# badgezadas.net
KiCad netlist of a schematic drawn in EAGLE
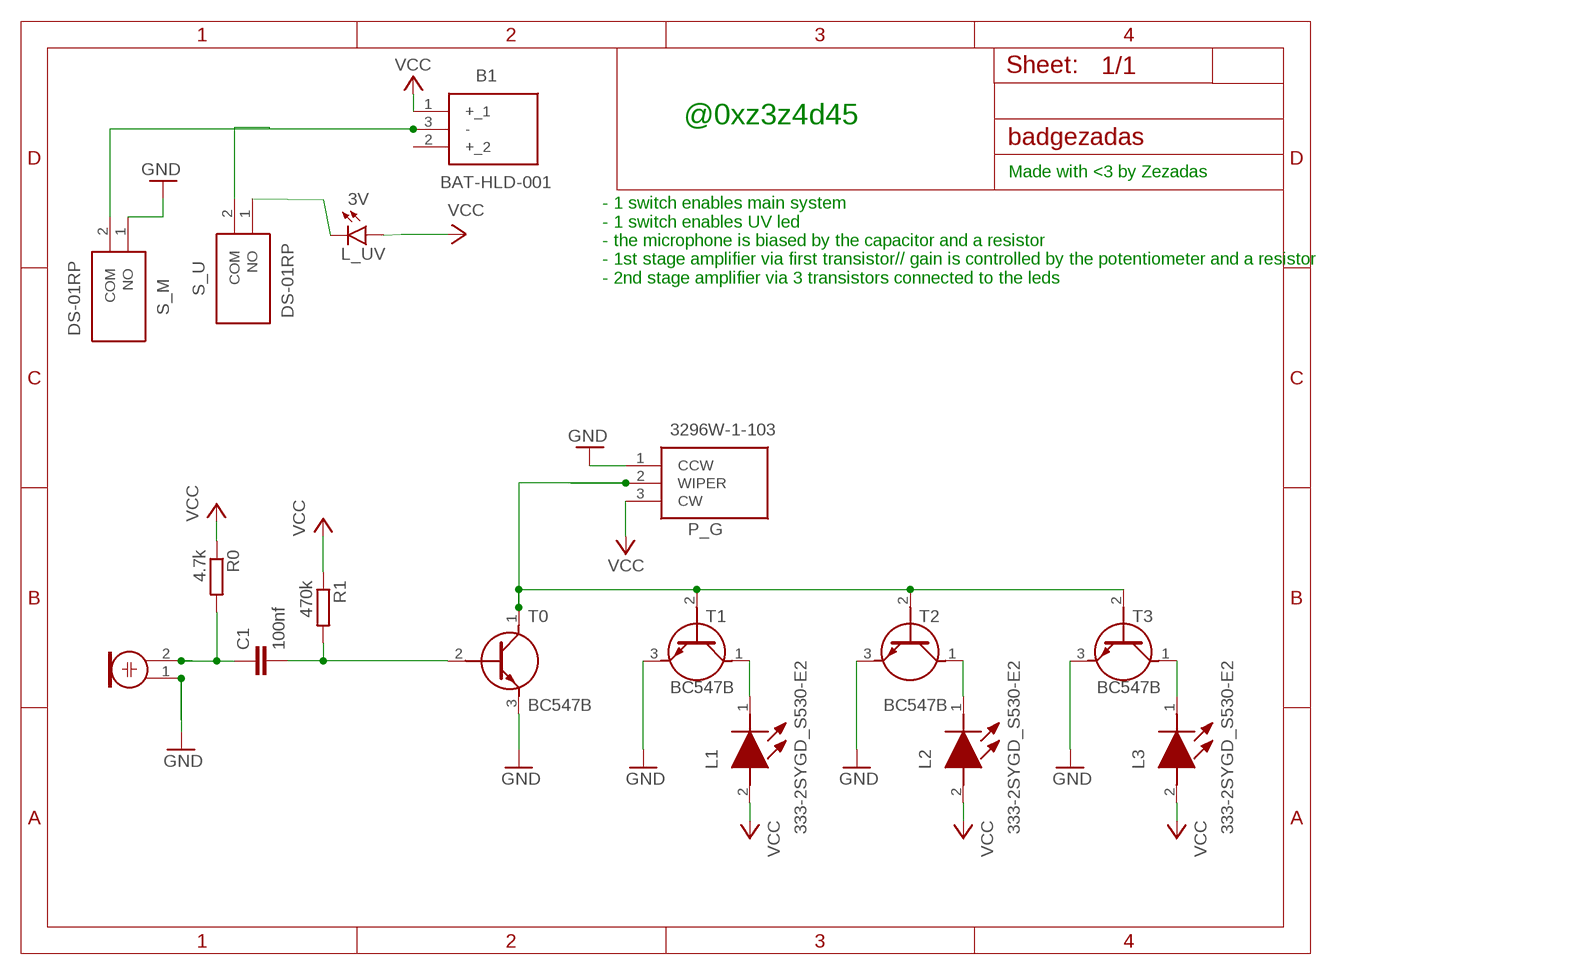
[diagram p0: schematic, sheet 1]

(export (version "E")
  (design (tool "Eeschema 10.0.6"))
  (components
    (comp (ref "B1")
      (value "BAT-HLD-001")
      (footprint "eagle-import:BATHLD001")
      (libsource (lib "eagle-import") (part "BAT-HLD-001"))
    )
    (comp (ref "C1")
      (value "100nf")
      (footprint "eagle-import:C025-024X044")
      (libsource (lib "eagle-import") (part "C-EU025-024X044"))
    )
    (comp (ref "L1")
      (value "333-2SYGD_S530-E2")
      (footprint "eagle-import:3332SYGDS530E2")
      (fields
        (field (name "ARROW_PART_NUMBER") "333-2SYGD/S530-E2")
        (field (name "MOUSER_PART_NUMBER") "638-333-2SYGDS5302")
      )
      (libsource (lib "eagle-import") (part "333-2SYGD_S530-E2"))
    )
    (comp (ref "L2")
      (value "333-2SYGD_S530-E2")
      (footprint "eagle-import:3332SYGDS530E2")
      (fields
        (field (name "ARROW_PART_NUMBER") "333-2SYGD/S530-E2")
        (field (name "MOUSER_PART_NUMBER") "638-333-2SYGDS5302")
      )
      (libsource (lib "eagle-import") (part "333-2SYGD_S530-E2"))
    )
    (comp (ref "L3")
      (value "333-2SYGD_S530-E2")
      (footprint "eagle-import:3332SYGDS530E2")
      (fields
        (field (name "ARROW_PART_NUMBER") "333-2SYGD/S530-E2")
        (field (name "MOUSER_PART_NUMBER") "638-333-2SYGDS5302")
      )
      (libsource (lib "eagle-import") (part "333-2SYGD_S530-E2"))
    )
    (comp (ref "L_UV")
      (value "3V")
      (footprint "eagle-import:LED3MM")
      (libsource (lib "eagle-import") (part "LED3MM"))
    )
    (comp (ref "M0")
      (value "ELECTRET_MICROPHON-F6050AP")
      (footprint "eagle-import:F6050AP")
      (libsource (lib "eagle-import") (part "ELECTRET_MICROPHON-F6050AP"))
    )
    (comp (ref "P_G")
      (value "3296W-1-103")
      (footprint "eagle-import:3296W1103")
      (fields (field (name "MOUSER_PART_NUMBER") "652-3296W-1-103"))
      (libsource (lib "eagle-import") (part "3296W-1-103"))
    )
    (comp (ref "R0")
      (value "4.7k")
      (footprint "eagle-import:0207_10")
      (libsource (lib "eagle-import") (part "R-EU_0207/10"))
    )
    (comp (ref "R1")
      (value "470k")
      (footprint "eagle-import:0207_10")
      (libsource (lib "eagle-import") (part "R-EU_0207/10"))
    )
    (comp (ref "S_M")
      (value "DS-01RP")
      (footprint "eagle-import:DS01RP")
      (libsource (lib "eagle-import") (part "DS-01RP"))
    )
    (comp (ref "S_U")
      (value "DS-01RP")
      (footprint "eagle-import:DS01RP")
      (libsource (lib "eagle-import") (part "DS-01RP"))
    )
    (comp (ref "T0")
      (value "BC547B")
      (footprint "eagle-import:TO-92-PLASTIC_2")
      (libsource (lib "eagle-import") (part "BC547B"))
    )
    (comp (ref "T1")
      (value "BC547B")
      (footprint "eagle-import:TO-92-PLASTIC_2")
      (libsource (lib "eagle-import") (part "BC547B"))
    )
    (comp (ref "T2")
      (value "BC547B")
      (footprint "eagle-import:TO-92-PLASTIC_2")
      (libsource (lib "eagle-import") (part "BC547B"))
    )
    (comp (ref "T3")
      (value "BC547B")
      (footprint "eagle-import:TO-92-PLASTIC_2")
      (libsource (lib "eagle-import") (part "BC547B"))
    )
  )
  (nets
    (net (code "1") (name "GND") (class "Default")
      (node (ref "M0") (pin "1") (pinfunction "1_1") (pintype "passive"))
      (node (ref "P_G") (pin "1") (pinfunction "CCW_1") (pintype "bidirectional"))
      (node (ref "S_M") (pin "1") (pinfunction "NO_1") (pintype "bidirectional"))
      (node (ref "T0") (pin "3") (pinfunction "E_3") (pintype "bidirectional"))
      (node (ref "T1") (pin "3") (pinfunction "E_3") (pintype "bidirectional"))
      (node (ref "T2") (pin "3") (pinfunction "E_3") (pintype "bidirectional"))
      (node (ref "T3") (pin "3") (pinfunction "E_3") (pintype "bidirectional"))
    )
    (net (code "2") (name "Net-(B1--)") (class "Default")
      (node (ref "B1") (pin "3") (pinfunction "-_3") (pintype "bidirectional"))
      (node (ref "S_M") (pin "2") (pinfunction "COM_2") (pintype "bidirectional"))
      (node (ref "S_U") (pin "2") (pinfunction "COM_2") (pintype "bidirectional"))
    )
    (net (code "3") (name "Net-(C1-Pad1)") (class "Default")
      (node (ref "C1") (pin "1") (pinfunction "1_1") (pintype "passive"))
      (node (ref "M0") (pin "2") (pinfunction "2_2") (pintype "passive"))
      (node (ref "R0") (pin "2") (pinfunction "2_2") (pintype "passive"))
    )
    (net (code "4") (name "Net-(L1-K)") (class "Default")
      (node (ref "L1") (pin "1") (pinfunction "K_1") (pintype "bidirectional"))
      (node (ref "T1") (pin "1") (pinfunction "C_1") (pintype "bidirectional"))
    )
    (net (code "5") (name "Net-(L2-K)") (class "Default")
      (node (ref "L2") (pin "1") (pinfunction "K_1") (pintype "bidirectional"))
      (node (ref "T2") (pin "1") (pinfunction "C_1") (pintype "bidirectional"))
    )
    (net (code "6") (name "Net-(L3-K)") (class "Default")
      (node (ref "L3") (pin "1") (pinfunction "K_1") (pintype "bidirectional"))
      (node (ref "T3") (pin "1") (pinfunction "C_1") (pintype "bidirectional"))
    )
    (net (code "7") (name "Net-(L_UV-C)") (class "Default")
      (node (ref "L_UV") (pin "K") (pinfunction "C_K") (pintype "passive"))
      (node (ref "S_U") (pin "1") (pinfunction "NO_1") (pintype "bidirectional"))
    )
    (net (code "8") (name "Net-(P_G-WIPER)") (class "Default")
      (node (ref "P_G") (pin "2") (pinfunction "WIPER_2") (pintype "bidirectional"))
      (node (ref "T0") (pin "1") (pinfunction "C_1") (pintype "bidirectional"))
      (node (ref "T1") (pin "2") (pinfunction "B_2") (pintype "bidirectional"))
      (node (ref "T2") (pin "2") (pinfunction "B_2") (pintype "bidirectional"))
      (node (ref "T3") (pin "2") (pinfunction "B_2") (pintype "bidirectional"))
    )
    (net (code "9") (name "Net-(T0-B)") (class "Default")
      (node (ref "C1") (pin "2") (pinfunction "2_2") (pintype "passive"))
      (node (ref "R1") (pin "2") (pinfunction "2_2") (pintype "passive"))
      (node (ref "T0") (pin "2") (pinfunction "B_2") (pintype "bidirectional"))
    )
    (net (code "10") (name "VCC") (class "Default")
      (node (ref "B1") (pin "1") (pinfunction "+_1_1") (pintype "bidirectional"))
      (node (ref "L1") (pin "2") (pinfunction "A_2") (pintype "bidirectional"))
      (node (ref "L2") (pin "2") (pinfunction "A_2") (pintype "bidirectional"))
      (node (ref "L3") (pin "2") (pinfunction "A_2") (pintype "bidirectional"))
      (node (ref "L_UV") (pin "A") (pinfunction "A_A") (pintype "passive"))
      (node (ref "P_G") (pin "3") (pinfunction "CW_3") (pintype "bidirectional"))
      (node (ref "R0") (pin "1") (pinfunction "1_1") (pintype "passive"))
      (node (ref "R1") (pin "1") (pinfunction "1_1") (pintype "passive"))
    )
    (net (code "11") (name "unconnected-(B1-+_2-Pad2)") (class "Default")
      (node (ref "B1") (pin "2") (pinfunction "+_2_2") (pintype "bidirectional"))
    )
  )
)
